# wirelessreceiver.net
KiCad netlist of a schematic drawn in EAGLE
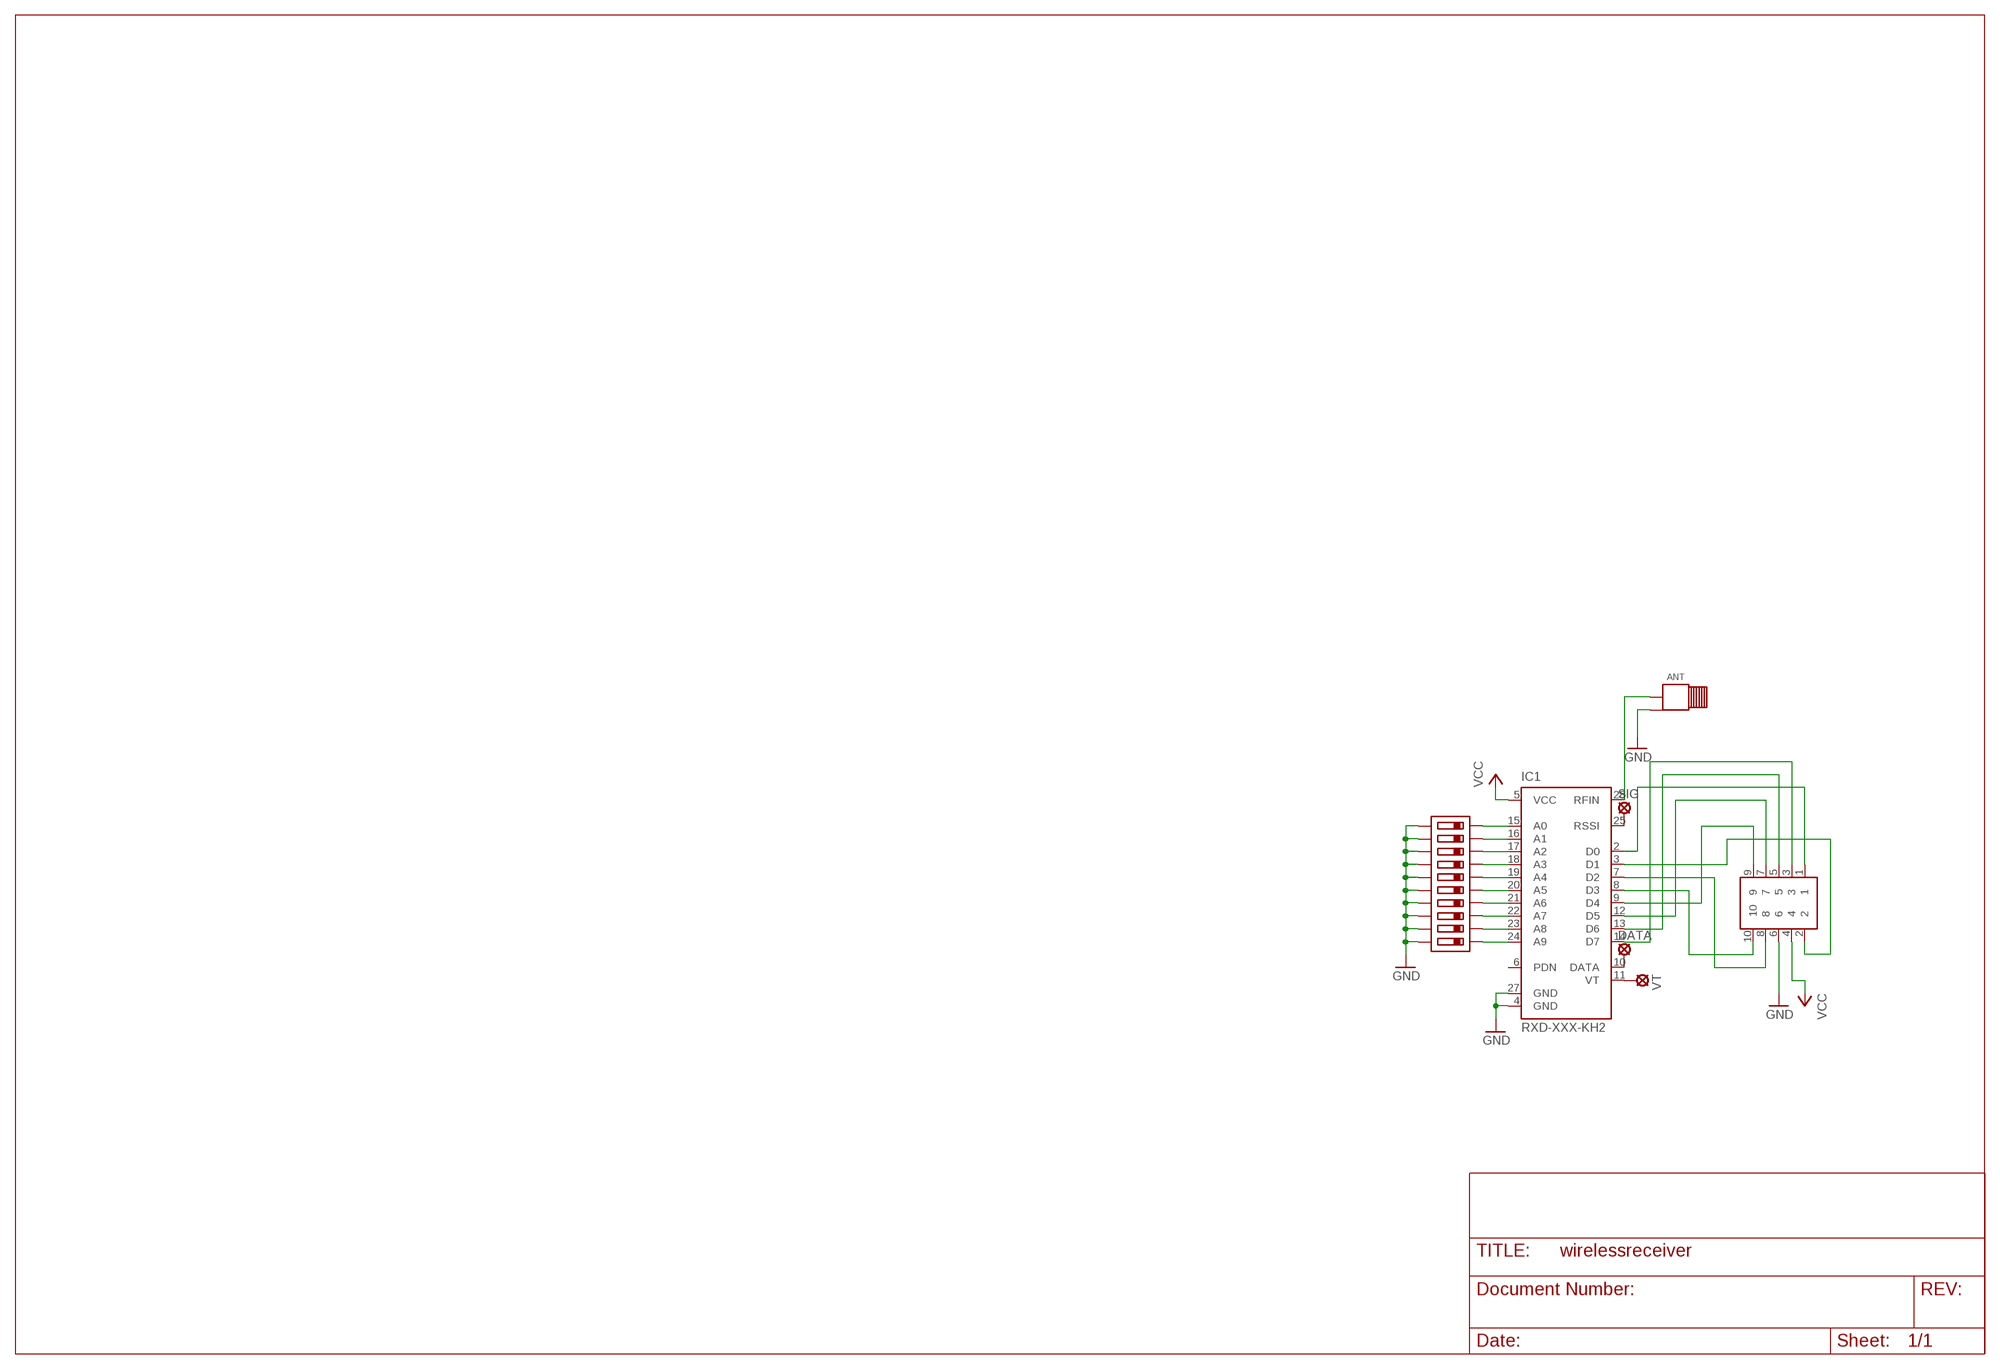
[diagram p0: schematic, sheet 1]

(export (version "E")
  (design (tool "Eeschema 10.0.6"))
  (components
    (comp (ref "ADDR")
      (value "CT21910MST")
      (footprint "eagle-import:CT21910MST")
      (libsource (lib "eagle-import") (part "CT21910MST"))
    )
    (comp (ref "ANT")
      (value "CONSMA002")
      (footprint "eagle-import:CONSMA002")
      (libsource (lib "eagle-import") (part "CONSMA002"))
    )
    (comp (ref "DATA")
      (value "MCS10B")
      (footprint "eagle-import:MCS10B")
      (libsource (lib "eagle-import") (part "MCS10B"))
    )
    (comp (ref "IC1")
      (value "RXD-XXX-KH2")
      (footprint "eagle-import:RXD-XXX-KH2")
      (libsource (lib "eagle-import") (part "RXD-XXX-KH2"))
    )
    (comp (ref "SIG")
      (value "MCS10B")
      (footprint "eagle-import:MCS10B")
      (libsource (lib "eagle-import") (part "MCS10B"))
    )
    (comp (ref "U$3")
      (value "2X5-PHEADER")
      (footprint "eagle-import:2X5-SHROUDED-HEADER")
      (libsource (lib "eagle-import") (part "2X5-PHEADER"))
    )
    (comp (ref "VT")
      (value "MCS10B")
      (footprint "eagle-import:MCS10B")
      (libsource (lib "eagle-import") (part "MCS10B"))
    )
  )
  (nets
    (net (code "1") (name "GND") (class "Default")
      (node (ref "ADDR") (pin "R0") (pinfunction "B9_R0") (pintype "bidirectional"))
      (node (ref "ADDR") (pin "R1") (pinfunction "B8_R1") (pintype "bidirectional"))
      (node (ref "ADDR") (pin "R2") (pinfunction "B7_R2") (pintype "bidirectional"))
      (node (ref "ADDR") (pin "R3") (pinfunction "B6_R3") (pintype "bidirectional"))
      (node (ref "ADDR") (pin "R4") (pinfunction "B5_R4") (pintype "bidirectional"))
      (node (ref "ADDR") (pin "R5") (pinfunction "B4_R5") (pintype "bidirectional"))
      (node (ref "ADDR") (pin "R6") (pinfunction "B3_R6") (pintype "bidirectional"))
      (node (ref "ADDR") (pin "R7") (pinfunction "B2_R7") (pintype "bidirectional"))
      (node (ref "ADDR") (pin "R8") (pinfunction "B1_R8") (pintype "bidirectional"))
      (node (ref "ADDR") (pin "R9") (pinfunction "B0_R9") (pintype "bidirectional"))
      (node (ref "ANT") (pin "GND") (pinfunction "GND_GND") (pintype "power_in"))
      (node (ref "ANT") (pin "GND1") (pinfunction "GND_GND1") (pintype "power_in"))
      (node (ref "ANT") (pin "GND2") (pinfunction "GND_GND2") (pintype "power_in"))
      (node (ref "ANT") (pin "GND3") (pinfunction "GND_GND3") (pintype "power_in"))
      (node (ref "IC1") (pin "27") (pinfunction "GND_27") (pintype "power_in"))
      (node (ref "IC1") (pin "4") (pinfunction "GND_4") (pintype "power_in"))
      (node (ref "U$3") (pin "6") (pinfunction "6_6") (pintype "bidirectional"))
    )
    (net (code "2") (name "Net-(ADDR-A0)") (class "Default")
      (node (ref "ADDR") (pin "L9") (pinfunction "A0_L9") (pintype "bidirectional"))
      (node (ref "IC1") (pin "15") (pinfunction "A0_15") (pintype "input"))
    )
    (net (code "3") (name "Net-(ADDR-A1)") (class "Default")
      (node (ref "ADDR") (pin "L8") (pinfunction "A1_L8") (pintype "bidirectional"))
      (node (ref "IC1") (pin "16") (pinfunction "A1_16") (pintype "input"))
    )
    (net (code "4") (name "Net-(ADDR-A2)") (class "Default")
      (node (ref "ADDR") (pin "L7") (pinfunction "A2_L7") (pintype "bidirectional"))
      (node (ref "IC1") (pin "17") (pinfunction "A2_17") (pintype "input"))
    )
    (net (code "5") (name "Net-(ADDR-A3)") (class "Default")
      (node (ref "ADDR") (pin "L6") (pinfunction "A3_L6") (pintype "bidirectional"))
      (node (ref "IC1") (pin "18") (pinfunction "A3_18") (pintype "input"))
    )
    (net (code "6") (name "Net-(ADDR-A4)") (class "Default")
      (node (ref "ADDR") (pin "L5") (pinfunction "A4_L5") (pintype "bidirectional"))
      (node (ref "IC1") (pin "19") (pinfunction "A4_19") (pintype "input"))
    )
    (net (code "7") (name "Net-(ADDR-A5)") (class "Default")
      (node (ref "ADDR") (pin "L4") (pinfunction "A5_L4") (pintype "bidirectional"))
      (node (ref "IC1") (pin "20") (pinfunction "A5_20") (pintype "input"))
    )
    (net (code "8") (name "Net-(ADDR-A6)") (class "Default")
      (node (ref "ADDR") (pin "L3") (pinfunction "A6_L3") (pintype "bidirectional"))
      (node (ref "IC1") (pin "21") (pinfunction "A6_21") (pintype "input"))
    )
    (net (code "9") (name "Net-(ADDR-A7)") (class "Default")
      (node (ref "ADDR") (pin "L2") (pinfunction "A7_L2") (pintype "bidirectional"))
      (node (ref "IC1") (pin "22") (pinfunction "A7_22") (pintype "input"))
    )
    (net (code "10") (name "Net-(ADDR-A8)") (class "Default")
      (node (ref "ADDR") (pin "L1") (pinfunction "A8_L1") (pintype "bidirectional"))
      (node (ref "IC1") (pin "23") (pinfunction "A8_23") (pintype "input"))
    )
    (net (code "11") (name "Net-(ADDR-A9)") (class "Default")
      (node (ref "ADDR") (pin "L0") (pinfunction "A9_L0") (pintype "bidirectional"))
      (node (ref "IC1") (pin "24") (pinfunction "A9_24") (pintype "input"))
    )
    (net (code "12") (name "Net-(IC1-D0)") (class "Default")
      (node (ref "IC1") (pin "2") (pinfunction "D0_2") (pintype "bidirectional"))
      (node (ref "U$3") (pin "1") (pinfunction "1_1") (pintype "bidirectional"))
    )
    (net (code "13") (name "Net-(IC1-D1)") (class "Default")
      (node (ref "IC1") (pin "3") (pinfunction "D1_3") (pintype "bidirectional"))
      (node (ref "U$3") (pin "2") (pinfunction "2_2") (pintype "bidirectional"))
    )
    (net (code "14") (name "Net-(IC1-D2)") (class "Default")
      (node (ref "IC1") (pin "7") (pinfunction "D2_7") (pintype "bidirectional"))
      (node (ref "U$3") (pin "8") (pinfunction "8_8") (pintype "bidirectional"))
    )
    (net (code "15") (name "Net-(IC1-D3)") (class "Default")
      (node (ref "IC1") (pin "8") (pinfunction "D3_8") (pintype "bidirectional"))
      (node (ref "U$3") (pin "10") (pinfunction "10_10") (pintype "bidirectional"))
    )
    (net (code "16") (name "Net-(IC1-D4)") (class "Default")
      (node (ref "IC1") (pin "9") (pinfunction "D4_9") (pintype "bidirectional"))
      (node (ref "U$3") (pin "9") (pinfunction "9_9") (pintype "bidirectional"))
    )
    (net (code "17") (name "Net-(IC1-D5)") (class "Default")
      (node (ref "IC1") (pin "12") (pinfunction "D5_12") (pintype "bidirectional"))
      (node (ref "U$3") (pin "7") (pinfunction "7_7") (pintype "bidirectional"))
    )
    (net (code "18") (name "Net-(IC1-D6)") (class "Default")
      (node (ref "IC1") (pin "13") (pinfunction "D6_13") (pintype "bidirectional"))
      (node (ref "U$3") (pin "5") (pinfunction "5_5") (pintype "bidirectional"))
    )
    (net (code "19") (name "Net-(IC1-D7)") (class "Default")
      (node (ref "IC1") (pin "14") (pinfunction "D7_14") (pintype "bidirectional"))
      (node (ref "U$3") (pin "3") (pinfunction "3_3") (pintype "bidirectional"))
    )
    (net (code "20") (name "Net-(IC1-DATA)") (class "Default")
      (node (ref "DATA") (pin "MP") (pinfunction "MP_MP") (pintype "passive"))
      (node (ref "IC1") (pin "10") (pinfunction "DATA_10") (pintype "output"))
    )
    (net (code "21") (name "Net-(IC1-RFIN)") (class "Default")
      (node (ref "ANT") (pin "ANT") (pinfunction "ANT_ANT") (pintype "output"))
      (node (ref "IC1") (pin "28") (pinfunction "RFIN_28") (pintype "input"))
    )
    (net (code "22") (name "Net-(IC1-RSSI)") (class "Default")
      (node (ref "IC1") (pin "25") (pinfunction "RSSI_25") (pintype "passive"))
      (node (ref "SIG") (pin "MP") (pinfunction "MP_MP") (pintype "passive"))
    )
    (net (code "23") (name "Net-(IC1-VT)") (class "Default")
      (node (ref "IC1") (pin "11") (pinfunction "VT_11") (pintype "output"))
      (node (ref "VT") (pin "MP") (pinfunction "MP_MP") (pintype "passive"))
    )
    (net (code "24") (name "VCC") (class "Default")
      (node (ref "IC1") (pin "5") (pinfunction "VCC_5") (pintype "power_in"))
      (node (ref "U$3") (pin "4") (pinfunction "4_4") (pintype "bidirectional"))
    )
    (net (code "25") (name "unconnected-(IC1-PDN-Pad6)") (class "Default")
      (node (ref "IC1") (pin "6") (pinfunction "PDN_6") (pintype "input"))
    )
  )
)
